# 1-Schematic_dirty_video_mixer.net
KiCad netlist of a schematic drawn in EasyEDA
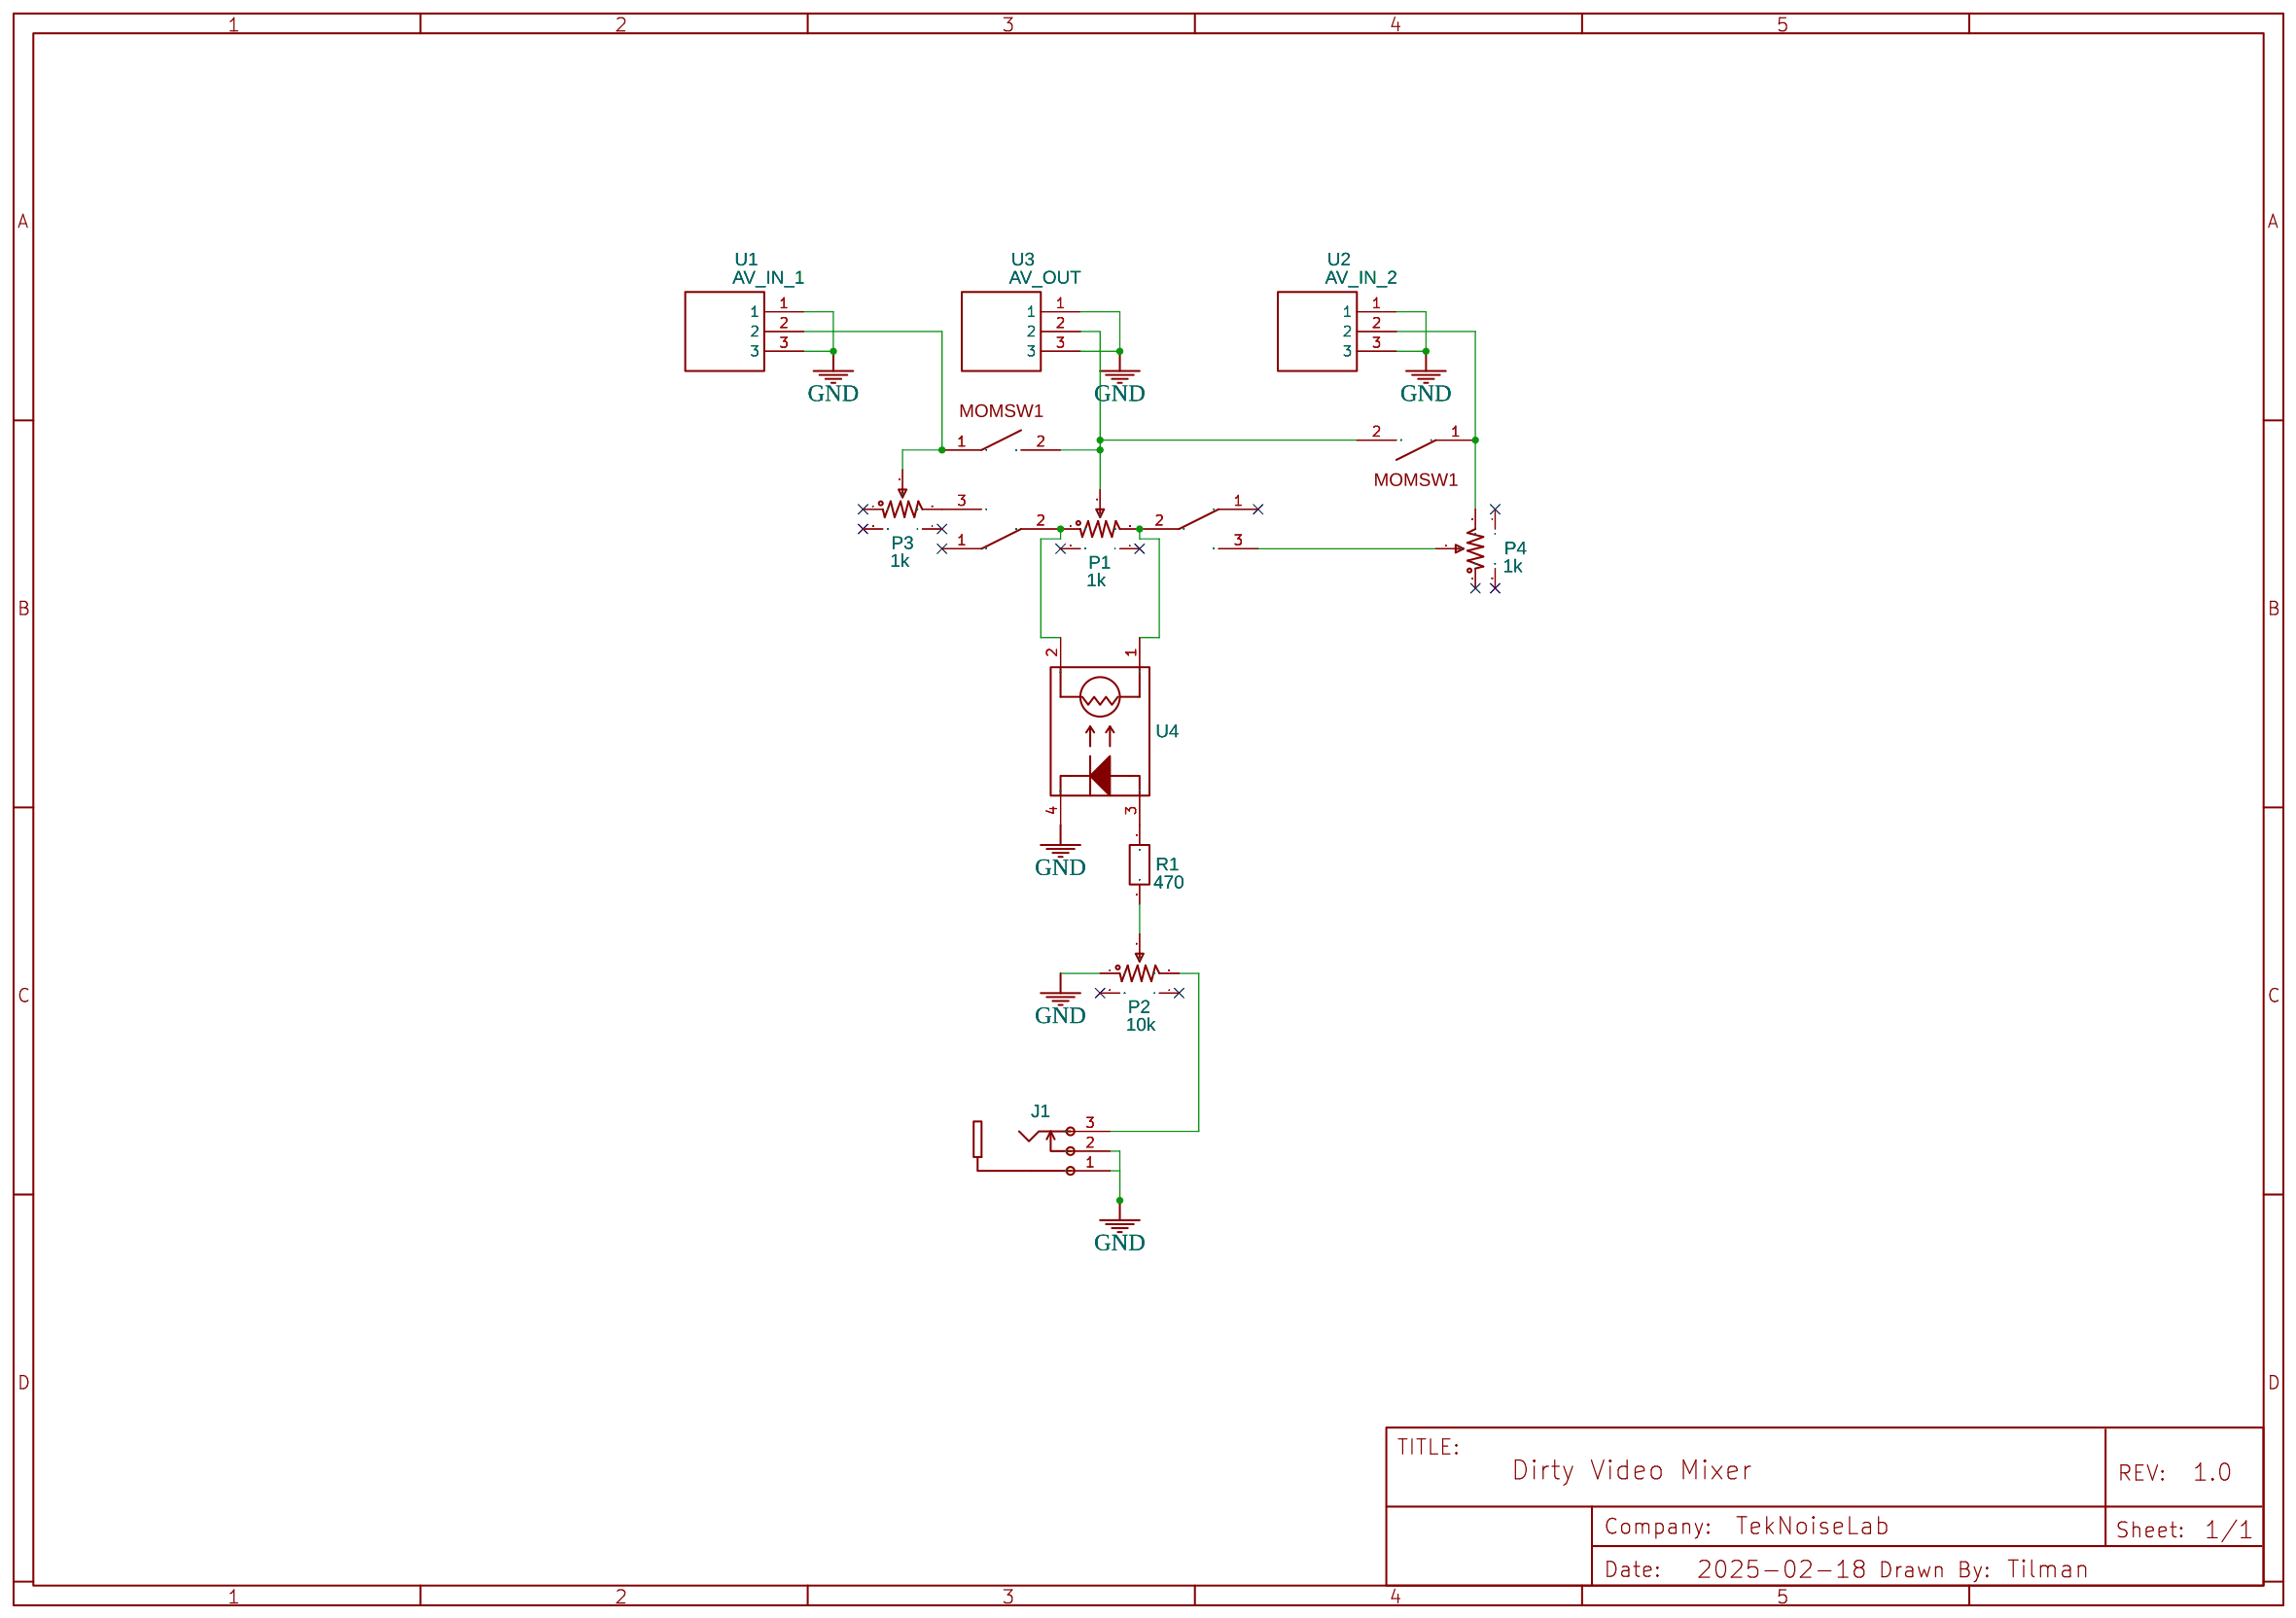
[diagram p0: schematic sheet]

(export (version "E")
  (design (tool "Eeschema 10.0.6"))
  (components
    (comp (ref "J1") (value "DESTROY") (libsource (lib "") (part "PJ-301M")))
    (comp (ref "P1")
      (value "1k")
      (fields
        (field (name "Manufacturer Part") "RK09K1130081")
        (field (name "Manufacturer") "ALPSALPINE(阿尔卑斯阿尔派)")
      )
      (libsource (lib "") (part "RK09K1130081"))
    )
    (comp (ref "P2")
      (value "10k")
      (fields
        (field (name "Manufacturer Part") "RK09K1130081")
        (field (name "Manufacturer") "ALPSALPINE(阿尔卑斯阿尔派)")
      )
      (libsource (lib "") (part "RK09K1130081"))
    )
    (comp (ref "P3")
      (value "1k")
      (fields
        (field (name "Manufacturer Part") "RK09K1130081")
        (field (name "Manufacturer") "ALPSALPINE(阿尔卑斯阿尔派)")
      )
      (libsource (lib "") (part "RK09K1130081"))
    )
    (comp (ref "P4")
      (value "1k")
      (fields
        (field (name "Manufacturer Part") "RK09K1130081")
        (field (name "Manufacturer") "ALPSALPINE(阿尔卑斯阿尔派)")
      )
      (libsource (lib "") (part "RK09K1130081_1"))
    )
    (comp (ref "R1") (value "470") (libsource (lib "") (part "Res_AXIAL-0.4(1/4W)_US")))
    (comp (ref "SW1") (value "MTS102 TOGGLE SWITCH") (libsource (lib "") (part "MTS102 TOGGLE SWITCH_1")))
    (comp (ref "SW2") (value "MTS102 TOGGLE SWITCH") (libsource (lib "") (part "MTS102 TOGGLE SWITCH")))
    (comp (ref "SW3") (value "MOM1") (libsource (lib "") (part "N.O. MOMENTARY SWITCH (6MM)")))
    (comp (ref "SW4") (value "MOM2") (libsource (lib "") (part "N.O. MOMENTARY SWITCH (6MM)_1")))
    (comp (ref "U1") (value "AV_IN_1") (libsource (lib "") (part "RCA_Female")))
    (comp (ref "U2") (value "AV_IN_2") (libsource (lib "") (part "RCA_Female")))
    (comp (ref "U3") (value "AV_OUT") (libsource (lib "") (part "RCA_Female")))
    (comp (ref "U4") (value "VTL5C8") (libsource (lib "") (part "VTL5C8")))
  )
  (nets
    (net (code "1") (name "GND") (class "Default")
      (node (ref "J1") (pin "1") (pinfunction "1_1") (pintype "unspecified"))
      (node (ref "J1") (pin "2") (pinfunction "2_2") (pintype "unspecified"))
      (node (ref "P2") (pin "1") (pinfunction "1_1") (pintype "unspecified"))
      (node (ref "U1") (pin "1") (pinfunction "1_1") (pintype "unspecified"))
      (node (ref "U1") (pin "3") (pinfunction "3_3") (pintype "unspecified"))
      (node (ref "U2") (pin "1") (pinfunction "1_1") (pintype "unspecified"))
      (node (ref "U2") (pin "3") (pinfunction "3_3") (pintype "unspecified"))
      (node (ref "U3") (pin "1") (pinfunction "1_1") (pintype "unspecified"))
      (node (ref "U3") (pin "3") (pinfunction "3_3") (pintype "unspecified"))
      (node (ref "U4") (pin "4") (pinfunction "C_4") (pintype "input"))
    )
    (net (code "2") (name "Net-(J1-Pad3)") (class "Default")
      (node (ref "J1") (pin "3") (pinfunction "3_3") (pintype "unspecified"))
      (node (ref "P2") (pin "3") (pinfunction "3_3") (pintype "unspecified"))
    )
    (net (code "3") (name "Net-(P1-Pad1)") (class "Default")
      (node (ref "P1") (pin "1") (pinfunction "1_1") (pintype "unspecified"))
      (node (ref "SW1") (pin "2") (pinfunction "2_2") (pintype "unspecified"))
      (node (ref "U4") (pin "2") (pinfunction "2_2") (pintype "input"))
    )
    (net (code "4") (name "Net-(P1-Pad2)") (class "Default")
      (node (ref "P1") (pin "2") (pinfunction "2_2") (pintype "unspecified"))
      (node (ref "SW3") (pin "2") (pinfunction "2_2") (pintype "unspecified"))
      (node (ref "SW4") (pin "2") (pinfunction "2_2") (pintype "unspecified"))
      (node (ref "U3") (pin "2") (pinfunction "2_2") (pintype "unspecified"))
    )
    (net (code "5") (name "Net-(P1-Pad3)") (class "Default")
      (node (ref "P1") (pin "3") (pinfunction "3_3") (pintype "unspecified"))
      (node (ref "SW2") (pin "2") (pinfunction "2_2") (pintype "unspecified"))
      (node (ref "U4") (pin "1") (pinfunction "1_1") (pintype "input"))
    )
    (net (code "6") (name "Net-(P2-Pad2)") (class "Default")
      (node (ref "P2") (pin "2") (pinfunction "2_2") (pintype "unspecified"))
      (node (ref "R1") (pin "2") (pinfunction "2_2") (pintype "unspecified"))
    )
    (net (code "7") (name "Net-(P3-Pad2)") (class "Default")
      (node (ref "P3") (pin "2") (pinfunction "2_2") (pintype "unspecified"))
      (node (ref "SW3") (pin "1") (pinfunction "1_1") (pintype "unspecified"))
      (node (ref "U1") (pin "2") (pinfunction "2_2") (pintype "unspecified"))
    )
    (net (code "8") (name "Net-(P3-Pad3)") (class "Default")
      (node (ref "P3") (pin "3") (pinfunction "3_3") (pintype "unspecified"))
      (node (ref "SW1") (pin "3") (pinfunction "3_3") (pintype "unspecified"))
    )
    (net (code "9") (name "Net-(P4-Pad2)") (class "Default")
      (node (ref "P4") (pin "2") (pinfunction "2_2") (pintype "unspecified"))
      (node (ref "SW2") (pin "3") (pinfunction "3_3") (pintype "unspecified"))
    )
    (net (code "10") (name "Net-(P4-Pad3)") (class "Default")
      (node (ref "P4") (pin "3") (pinfunction "3_3") (pintype "unspecified"))
      (node (ref "SW4") (pin "1") (pinfunction "1_1") (pintype "unspecified"))
      (node (ref "U2") (pin "2") (pinfunction "2_2") (pintype "unspecified"))
    )
    (net (code "11") (name "Net-(U4-A)") (class "Default")
      (node (ref "R1") (pin "1") (pinfunction "1_1") (pintype "unspecified"))
      (node (ref "U4") (pin "3") (pinfunction "A_3") (pintype "input"))
    )
    (net (code "12") (name "unconnected-(P1-Pad4)") (class "Default")
      (node (ref "P1") (pin "4") (pinfunction "4_4") (pintype "unspecified+no_connect"))
    )
    (net (code "13") (name "unconnected-(P1-Pad5)") (class "Default")
      (node (ref "P1") (pin "5") (pinfunction "5_5") (pintype "unspecified+no_connect"))
    )
    (net (code "14") (name "unconnected-(P2-Pad4)") (class "Default")
      (node (ref "P2") (pin "4") (pinfunction "4_4") (pintype "unspecified+no_connect"))
    )
    (net (code "15") (name "unconnected-(P2-Pad5)") (class "Default")
      (node (ref "P2") (pin "5") (pinfunction "5_5") (pintype "unspecified+no_connect"))
    )
    (net (code "16") (name "unconnected-(P3-Pad1)") (class "Default")
      (node (ref "P3") (pin "1") (pinfunction "1_1") (pintype "unspecified+no_connect"))
    )
    (net (code "17") (name "unconnected-(P3-Pad4)") (class "Default")
      (node (ref "P3") (pin "4") (pinfunction "4_4") (pintype "unspecified+no_connect"))
    )
    (net (code "18") (name "unconnected-(P3-Pad5)") (class "Default")
      (node (ref "P3") (pin "5") (pinfunction "5_5") (pintype "unspecified+no_connect"))
    )
    (net (code "19") (name "unconnected-(P4-Pad1)") (class "Default")
      (node (ref "P4") (pin "1") (pinfunction "1_1") (pintype "unspecified+no_connect"))
    )
    (net (code "20") (name "unconnected-(P4-Pad4)") (class "Default")
      (node (ref "P4") (pin "4") (pinfunction "4_4") (pintype "unspecified+no_connect"))
    )
    (net (code "21") (name "unconnected-(P4-Pad5)") (class "Default")
      (node (ref "P4") (pin "5") (pinfunction "5_5") (pintype "unspecified+no_connect"))
    )
    (net (code "22") (name "unconnected-(SW1-Pad1)") (class "Default")
      (node (ref "SW1") (pin "1") (pinfunction "1_1") (pintype "unspecified+no_connect"))
    )
    (net (code "23") (name "unconnected-(SW2-Pad1)") (class "Default")
      (node (ref "SW2") (pin "1") (pinfunction "1_1") (pintype "unspecified+no_connect"))
    )
  )
)
